# SFT_MotorController1_2v.net
KiCad netlist of a schematic drawn in EAGLE
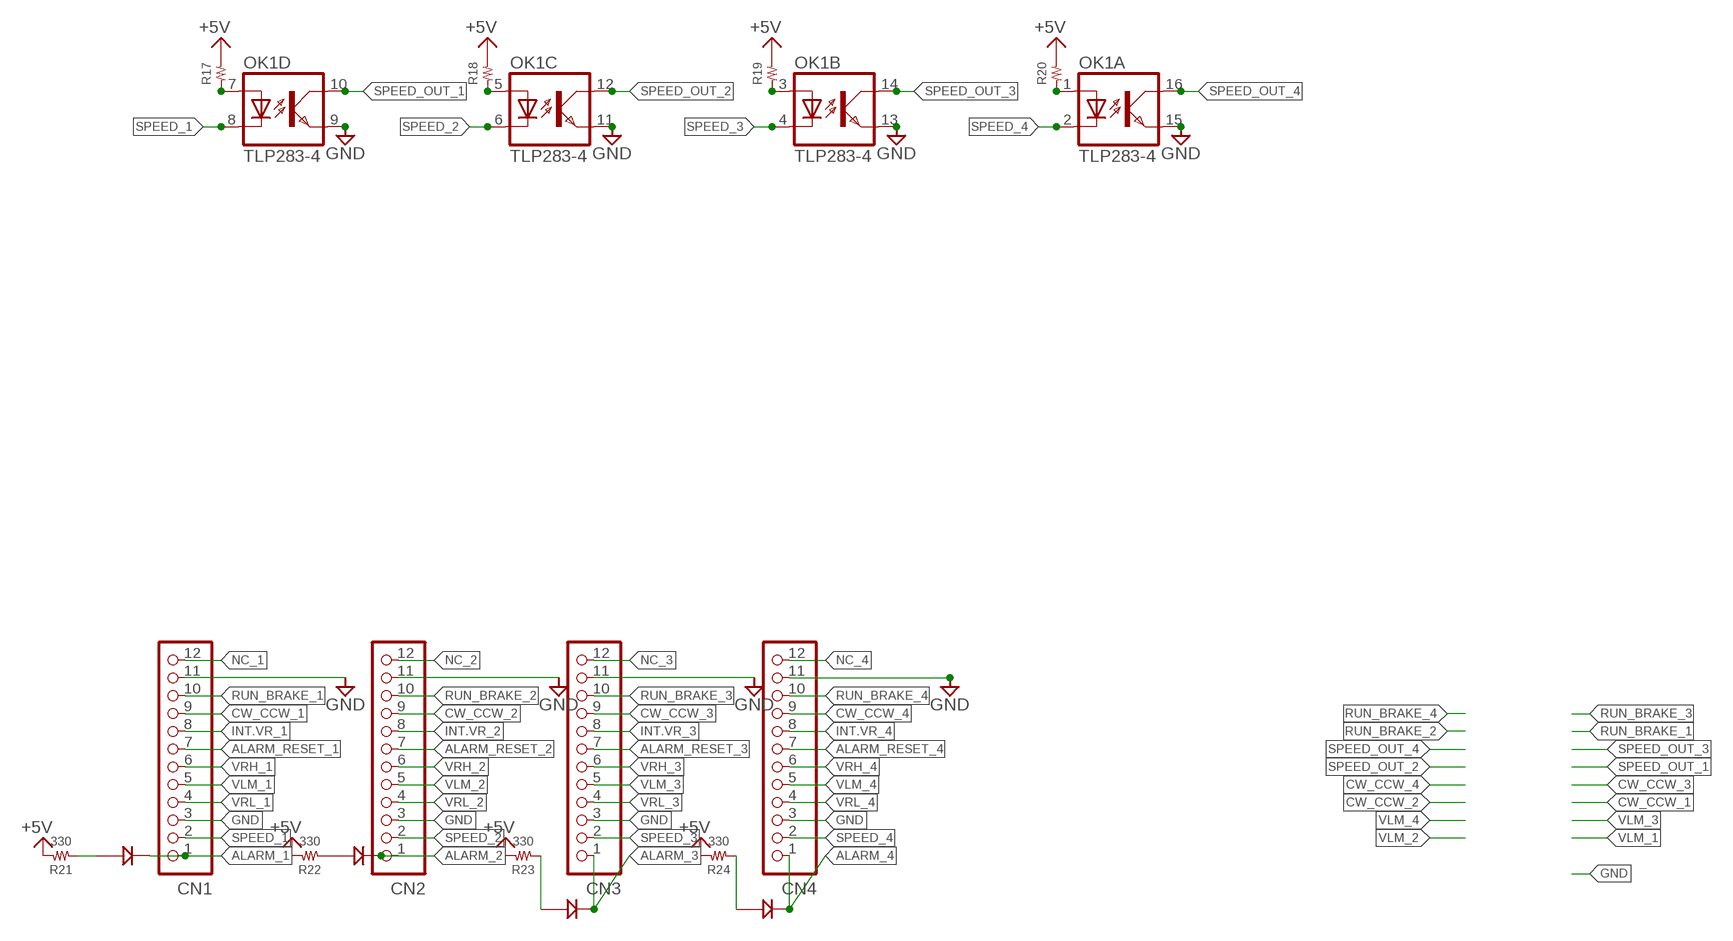
[diagram p0: schematic, sheet 1, part 1 of 2]
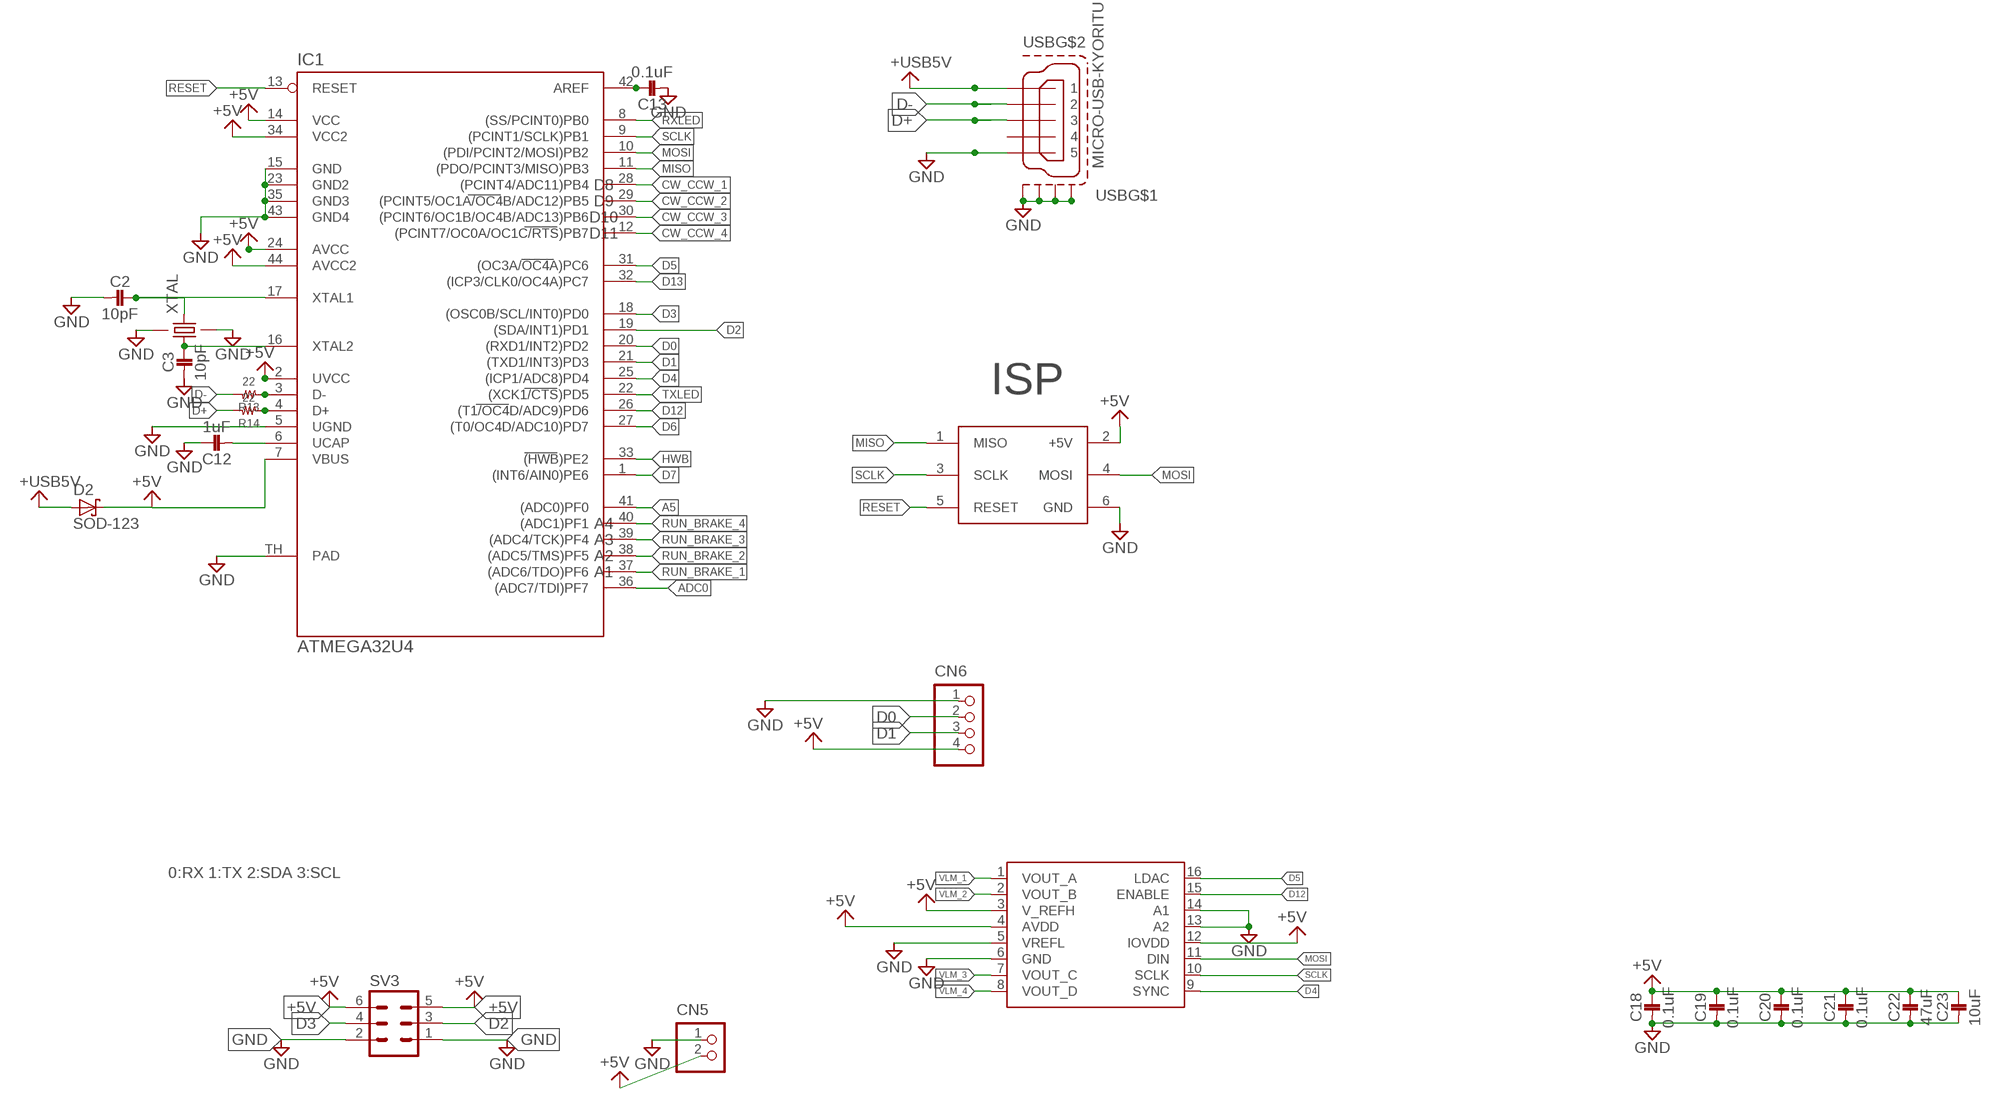
[diagram p1: schematic, sheet 1, part 2 of 2]

(export (version "E")
  (design (tool "Eeschema 10.0.6"))
  (components
    (comp (ref "C2")
      (value "10pF")
      (footprint "eagle-import:1005")
      (libsource (lib "eagle-import") (part "1005"))
    )
    (comp (ref "C3")
      (value "10pF")
      (footprint "eagle-import:1005")
      (libsource (lib "eagle-import") (part "1005"))
    )
    (comp (ref "C12")
      (value "1uF")
      (footprint "eagle-import:1005")
      (libsource (lib "eagle-import") (part "1005"))
    )
    (comp (ref "C13")
      (value "0.1uF")
      (footprint "eagle-import:1005")
      (libsource (lib "eagle-import") (part "1005"))
    )
    (comp (ref "C18")
      (value "0.1uF")
      (footprint "eagle-import:1005")
      (libsource (lib "eagle-import") (part "1005"))
    )
    (comp (ref "C19")
      (value "0.1uF")
      (footprint "eagle-import:1005")
      (libsource (lib "eagle-import") (part "1005"))
    )
    (comp (ref "C20")
      (value "0.1uF")
      (footprint "eagle-import:1005")
      (libsource (lib "eagle-import") (part "1005"))
    )
    (comp (ref "C21")
      (value "0.1uF")
      (footprint "eagle-import:1005")
      (libsource (lib "eagle-import") (part "1005"))
    )
    (comp (ref "C22")
      (value "47uF")
      (footprint "eagle-import:1608")
      (libsource (lib "eagle-import") (part "1608"))
    )
    (comp (ref "C23")
      (value "10uF")
      (footprint "eagle-import:1608")
      (libsource (lib "eagle-import") (part "1608"))
    )
    (comp (ref "CN1")
      (value "B12B-XASK-1")
      (footprint "eagle-import:B12B-XASK-1")
      (libsource (lib "eagle-import") (part "B12B-XASK-1"))
    )
    (comp (ref "CN2")
      (value "B12B-XASK-1")
      (footprint "eagle-import:B12B-XASK-1")
      (libsource (lib "eagle-import") (part "B12B-XASK-1"))
    )
    (comp (ref "CN3")
      (value "B12B-XASK-1")
      (footprint "eagle-import:B12B-XASK-1")
      (libsource (lib "eagle-import") (part "B12B-XASK-1"))
    )
    (comp (ref "CN4")
      (value "B12B-XASK-1")
      (footprint "eagle-import:B12B-XASK-1")
      (libsource (lib "eagle-import") (part "B12B-XASK-1"))
    )
    (comp (ref "CN5")
      (value "B2B-XASK-1")
      (footprint "eagle-import:B2B-XASK-1")
      (libsource (lib "eagle-import") (part "B2B-XASK-1"))
    )
    (comp (ref "CN6")
      (value "B4B-XASK-1")
      (footprint "eagle-import:B4B-XASK-1")
      (libsource (lib "eagle-import") (part "B4B-XASK-1"))
    )
    (comp (ref "D2")
      (value "SOD-123")
      (footprint "eagle-import:SOD_123")
      (libsource (lib "eagle-import") (part "SOD-123"))
    )
    (comp (ref "IC1")
      (value "ATMEGA32U4")
      (footprint "eagle-import:QFN-44-7X7")
      (libsource (lib "eagle-import") (part "ATMEGA32U4"))
    )
    (comp (ref "IC3")
      (value "DAC7564")
      (footprint "eagle-import:TSSOP16")
      (libsource (lib "eagle-import") (part "DAC7564"))
    )
    (comp (ref "OK1")
      (value "TLP283-4")
      (footprint "eagle-import:MINI-FLAT-16")
      (libsource (lib "eagle-import") (part "TLP283-4"))
    )
    (comp (ref "R13")
      (value "22")
      (footprint "eagle-import:1005")
      (libsource (lib "eagle-import") (part "RESISTOR_1005"))
    )
    (comp (ref "R14")
      (value "22")
      (footprint "eagle-import:1005")
      (libsource (lib "eagle-import") (part "RESISTOR_1005"))
    )
    (comp (ref "R17")
      (value "RESISTOR__SMD")
      (footprint "eagle-import:1608")
      (libsource (lib "eagle-import") (part "RESISTOR__SMD"))
    )
    (comp (ref "R18")
      (value "RESISTOR__SMD")
      (footprint "eagle-import:1608")
      (libsource (lib "eagle-import") (part "RESISTOR__SMD"))
    )
    (comp (ref "R19")
      (value "RESISTOR__SMD")
      (footprint "eagle-import:1608")
      (libsource (lib "eagle-import") (part "RESISTOR__SMD"))
    )
    (comp (ref "R20")
      (value "RESISTOR__SMD")
      (footprint "eagle-import:1608")
      (libsource (lib "eagle-import") (part "RESISTOR__SMD"))
    )
    (comp (ref "R21")
      (value "330")
      (footprint "eagle-import:1608")
      (libsource (lib "eagle-import") (part "RESISTOR__SMD"))
    )
    (comp (ref "R22")
      (value "330")
      (footprint "eagle-import:1608")
      (libsource (lib "eagle-import") (part "RESISTOR__SMD"))
    )
    (comp (ref "R23")
      (value "330")
      (footprint "eagle-import:1608")
      (libsource (lib "eagle-import") (part "RESISTOR__SMD"))
    )
    (comp (ref "R24")
      (value "330")
      (footprint "eagle-import:1608")
      (libsource (lib "eagle-import") (part "RESISTOR__SMD"))
    )
    (comp (ref "SV3")
      (value "ML6")
      (footprint "eagle-import:ML6")
      (libsource (lib "eagle-import") (part "ML6"))
    )
    (comp (ref "U$8")
      (value "ICSP")
      (footprint "eagle-import:ICSP")
      (libsource (lib "eagle-import") (part "ICSP"))
    )
    (comp (ref "U$36")
      (value "3MMLED")
      (footprint "eagle-import:3MM")
      (libsource (lib "eagle-import") (part "3MMLED"))
    )
    (comp (ref "U$37")
      (value "3MMLED")
      (footprint "eagle-import:3MM")
      (libsource (lib "eagle-import") (part "3MMLED"))
    )
    (comp (ref "U$38")
      (value "3MMLED")
      (footprint "eagle-import:3MM")
      (libsource (lib "eagle-import") (part "3MMLED"))
    )
    (comp (ref "U$39")
      (value "3MMLED")
      (footprint "eagle-import:3MM")
      (libsource (lib "eagle-import") (part "3MMLED"))
    )
    (comp (ref "USB")
      (value "MICRO-USB-KYORITU")
      (footprint "eagle-import:ZX62R-B-5P")
      (libsource (lib "eagle-import") (part "MICRO-USB-KYORITU"))
    )
    (comp (ref "XTAL")
      (value "FA-238")
      (footprint "eagle-import:FA-238")
      (libsource (lib "eagle-import") (part "FA-238"))
    )
  )
  (nets
    (net (code "1") (name "+5V") (class "Default")
      (node (ref "C18") (pin "1") (pinfunction "1_1") (pintype "passive"))
      (node (ref "C19") (pin "1") (pinfunction "1_1") (pintype "passive"))
      (node (ref "C20") (pin "1") (pinfunction "1_1") (pintype "passive"))
      (node (ref "C21") (pin "1") (pinfunction "1_1") (pintype "passive"))
      (node (ref "C22") (pin "P$1") (pinfunction "1_P$1") (pintype "passive"))
      (node (ref "C23") (pin "P$1") (pinfunction "1_P$1") (pintype "passive"))
      (node (ref "CN5") (pin "2") (pinfunction "2_2") (pintype "passive"))
      (node (ref "CN6") (pin "4") (pinfunction "4_4") (pintype "passive"))
      (node (ref "D2") (pin "C") (pinfunction "C_C") (pintype "passive"))
      (node (ref "IC1") (pin "14") (pinfunction "VCC_14") (pintype "bidirectional"))
      (node (ref "IC1") (pin "2") (pinfunction "UVCC_2") (pintype "bidirectional"))
      (node (ref "IC1") (pin "24") (pinfunction "AVCC_24") (pintype "bidirectional"))
      (node (ref "IC1") (pin "34") (pinfunction "VCC2_34") (pintype "bidirectional"))
      (node (ref "IC1") (pin "44") (pinfunction "AVCC2_44") (pintype "bidirectional"))
      (node (ref "IC1") (pin "7") (pinfunction "VBUS_7") (pintype "bidirectional"))
      (node (ref "IC3") (pin "12") (pinfunction "IOVDD_12") (pintype "bidirectional"))
      (node (ref "IC3") (pin "3") (pinfunction "V_REFH_3") (pintype "bidirectional"))
      (node (ref "IC3") (pin "4") (pinfunction "AVDD_4") (pintype "bidirectional"))
      (node (ref "R17") (pin "2") (pinfunction "P$2_2") (pintype "passive"))
      (node (ref "R18") (pin "2") (pinfunction "P$2_2") (pintype "passive"))
      (node (ref "R19") (pin "2") (pinfunction "P$2_2") (pintype "passive"))
      (node (ref "R20") (pin "2") (pinfunction "P$2_2") (pintype "passive"))
      (node (ref "R21") (pin "2") (pinfunction "P$2_2") (pintype "passive"))
      (node (ref "R22") (pin "2") (pinfunction "P$2_2") (pintype "passive"))
      (node (ref "R23") (pin "2") (pinfunction "P$2_2") (pintype "passive"))
      (node (ref "R24") (pin "2") (pinfunction "P$2_2") (pintype "passive"))
      (node (ref "SV3") (pin "5") (pinfunction "5_5") (pintype "passive"))
      (node (ref "SV3") (pin "6") (pinfunction "6_6") (pintype "passive"))
      (node (ref "U$8") (pin "2") (pinfunction "+5V_2") (pintype "bidirectional"))
    )
    (net (code "2") (name "+USB5V") (class "Default")
      (node (ref "D2") (pin "A") (pinfunction "A_A") (pintype "passive"))
      (node (ref "USB") (pin "5") (pinfunction "1_5") (pintype "input"))
    )
    (net (code "3") (name "A5") (class "Default")
      (node (ref "IC1") (pin "41") (pinfunction "(ADC0)PF0_41") (pintype "bidirectional"))
    )
    (net (code "4") (name "ADC0") (class "Default")
      (node (ref "IC1") (pin "36") (pinfunction "(ADC7/TDI)PF7_36") (pintype "bidirectional"))
    )
    (net (code "5") (name "ALARM_1") (class "Default")
      (node (ref "CN1") (pin "1") (pinfunction "1_1") (pintype "passive"))
      (node (ref "U$37") (pin "K") (pinfunction "K_K") (pintype "bidirectional"))
    )
    (net (code "6") (name "ALARM_2") (class "Default")
      (node (ref "CN2") (pin "1") (pinfunction "1_1") (pintype "passive"))
      (node (ref "U$38") (pin "K") (pinfunction "K_K") (pintype "bidirectional"))
    )
    (net (code "7") (name "ALARM_3") (class "Default")
      (node (ref "CN3") (pin "1") (pinfunction "1_1") (pintype "passive"))
      (node (ref "U$36") (pin "K") (pinfunction "K_K") (pintype "bidirectional"))
    )
    (net (code "8") (name "ALARM_4") (class "Default")
      (node (ref "CN4") (pin "1") (pinfunction "1_1") (pintype "passive"))
      (node (ref "U$39") (pin "K") (pinfunction "K_K") (pintype "bidirectional"))
    )
    (net (code "9") (name "ALARM_RESET_1") (class "Default")
      (node (ref "CN1") (pin "7") (pinfunction "7_7") (pintype "passive"))
    )
    (net (code "10") (name "ALARM_RESET_2") (class "Default")
      (node (ref "CN2") (pin "7") (pinfunction "7_7") (pintype "passive"))
    )
    (net (code "11") (name "ALARM_RESET_3") (class "Default")
      (node (ref "CN3") (pin "7") (pinfunction "7_7") (pintype "passive"))
    )
    (net (code "12") (name "ALARM_RESET_4") (class "Default")
      (node (ref "CN4") (pin "7") (pinfunction "7_7") (pintype "passive"))
    )
    (net (code "13") (name "CW_CCW_1") (class "Default")
      (node (ref "CN1") (pin "9") (pinfunction "9_9") (pintype "passive"))
      (node (ref "IC1") (pin "28") (pinfunction "(PCINT4/ADC11)PB4_28") (pintype "bidirectional"))
    )
    (net (code "14") (name "CW_CCW_2") (class "Default")
      (node (ref "CN2") (pin "9") (pinfunction "9_9") (pintype "passive"))
      (node (ref "IC1") (pin "29") (pinfunction "(PCINT5/OC1A/OC4B/ADC12)PB5_29") (pintype "bidirectional"))
    )
    (net (code "15") (name "CW_CCW_3") (class "Default")
      (node (ref "CN3") (pin "9") (pinfunction "9_9") (pintype "passive"))
      (node (ref "IC1") (pin "30") (pinfunction "(PCINT6/OC1B/OC4B/ADC13)PB6_30") (pintype "bidirectional"))
    )
    (net (code "16") (name "CW_CCW_4") (class "Default")
      (node (ref "CN4") (pin "9") (pinfunction "9_9") (pintype "passive"))
      (node (ref "IC1") (pin "12") (pinfunction "(PCINT7/OC0A/OC1C/RTS)PB7_12") (pintype "bidirectional"))
    )
    (net (code "17") (name "D+") (class "Default")
      (node (ref "R14") (pin "2") (pinfunction "P$2_2") (pintype "passive"))
      (node (ref "USB") (pin "3") (pinfunction "3_3") (pintype "input"))
    )
    (net (code "18") (name "D-") (class "Default")
      (node (ref "R13") (pin "2") (pinfunction "P$2_2") (pintype "passive"))
      (node (ref "USB") (pin "4") (pinfunction "2_4") (pintype "input"))
    )
    (net (code "19") (name "D0") (class "Default")
      (node (ref "CN6") (pin "2") (pinfunction "2_2") (pintype "passive"))
      (node (ref "IC1") (pin "20") (pinfunction "(RXD1/INT2)PD2_20") (pintype "bidirectional"))
    )
    (net (code "20") (name "D1") (class "Default")
      (node (ref "CN6") (pin "3") (pinfunction "3_3") (pintype "passive"))
      (node (ref "IC1") (pin "21") (pinfunction "(TXD1/INT3)PD3_21") (pintype "bidirectional"))
    )
    (net (code "21") (name "D2") (class "Default")
      (node (ref "IC1") (pin "19") (pinfunction "(SDA/INT1)PD1_19") (pintype "bidirectional"))
      (node (ref "SV3") (pin "3") (pinfunction "3_3") (pintype "passive"))
    )
    (net (code "22") (name "D3") (class "Default")
      (node (ref "IC1") (pin "18") (pinfunction "(OSC0B/SCL/INT0)PD0_18") (pintype "bidirectional"))
      (node (ref "SV3") (pin "4") (pinfunction "4_4") (pintype "passive"))
    )
    (net (code "23") (name "D4") (class "Default")
      (node (ref "IC1") (pin "25") (pinfunction "(ICP1/ADC8)PD4_25") (pintype "bidirectional"))
      (node (ref "IC3") (pin "9") (pinfunction "SYNC_9") (pintype "bidirectional"))
    )
    (net (code "24") (name "D5") (class "Default")
      (node (ref "IC1") (pin "31") (pinfunction "(OC3A/OC4A)PC6_31") (pintype "bidirectional"))
      (node (ref "IC3") (pin "16") (pinfunction "LDAC_16") (pintype "bidirectional"))
    )
    (net (code "25") (name "D6") (class "Default")
      (node (ref "IC1") (pin "27") (pinfunction "(T0/OC4D/ADC10)PD7_27") (pintype "bidirectional"))
    )
    (net (code "26") (name "D7") (class "Default")
      (node (ref "IC1") (pin "1") (pinfunction "(INT6/AIN0)PE6_1") (pintype "bidirectional"))
    )
    (net (code "27") (name "D12") (class "Default")
      (node (ref "IC1") (pin "26") (pinfunction "(T1/OC4D/ADC9)PD6_26") (pintype "bidirectional"))
      (node (ref "IC3") (pin "15") (pinfunction "ENABLE_15") (pintype "bidirectional"))
    )
    (net (code "28") (name "D13") (class "Default")
      (node (ref "IC1") (pin "32") (pinfunction "(ICP3/CLK0/OC4A)PC7_32") (pintype "bidirectional"))
    )
    (net (code "29") (name "GND") (class "Default")
      (node (ref "C12") (pin "1") (pinfunction "1_1") (pintype "passive"))
      (node (ref "C13") (pin "2") (pinfunction "2_2") (pintype "passive"))
      (node (ref "C18") (pin "2") (pinfunction "2_2") (pintype "passive"))
      (node (ref "C19") (pin "2") (pinfunction "2_2") (pintype "passive"))
      (node (ref "C2") (pin "2") (pinfunction "2_2") (pintype "passive"))
      (node (ref "C20") (pin "2") (pinfunction "2_2") (pintype "passive"))
      (node (ref "C21") (pin "2") (pinfunction "2_2") (pintype "passive"))
      (node (ref "C22") (pin "P$2") (pinfunction "2_P$2") (pintype "passive"))
      (node (ref "C23") (pin "P$2") (pinfunction "2_P$2") (pintype "passive"))
      (node (ref "C3") (pin "2") (pinfunction "2_2") (pintype "passive"))
      (node (ref "CN1") (pin "11") (pinfunction "11_11") (pintype "passive"))
      (node (ref "CN1") (pin "3") (pinfunction "3_3") (pintype "passive"))
      (node (ref "CN2") (pin "11") (pinfunction "11_11") (pintype "passive"))
      (node (ref "CN2") (pin "3") (pinfunction "3_3") (pintype "passive"))
      (node (ref "CN3") (pin "11") (pinfunction "11_11") (pintype "passive"))
      (node (ref "CN3") (pin "3") (pinfunction "3_3") (pintype "passive"))
      (node (ref "CN4") (pin "11") (pinfunction "11_11") (pintype "passive"))
      (node (ref "CN4") (pin "3") (pinfunction "3_3") (pintype "passive"))
      (node (ref "CN5") (pin "1") (pinfunction "1_1") (pintype "passive"))
      (node (ref "CN6") (pin "1") (pinfunction "1_1") (pintype "passive"))
      (node (ref "IC1") (pin "15") (pinfunction "GND_15") (pintype "bidirectional"))
      (node (ref "IC1") (pin "23") (pinfunction "GND2_23") (pintype "bidirectional"))
      (node (ref "IC1") (pin "35") (pinfunction "GND3_35") (pintype "bidirectional"))
      (node (ref "IC1") (pin "43") (pinfunction "GND4_43") (pintype "bidirectional"))
      (node (ref "IC1") (pin "5") (pinfunction "UGND_5") (pintype "bidirectional"))
      (node (ref "IC1") (pin "TH") (pinfunction "PAD_TH") (pintype "bidirectional"))
      (node (ref "IC3") (pin "13") (pinfunction "A2_13") (pintype "bidirectional"))
      (node (ref "IC3") (pin "14") (pinfunction "A1_14") (pintype "bidirectional"))
      (node (ref "IC3") (pin "5") (pinfunction "VREFL_5") (pintype "bidirectional"))
      (node (ref "IC3") (pin "6") (pinfunction "GND_6") (pintype "bidirectional"))
      (node (ref "OK1") (pin "11") (pinfunction "EMIT_11") (pintype "passive"))
      (node (ref "OK1") (pin "13") (pinfunction "EMIT_13") (pintype "passive"))
      (node (ref "OK1") (pin "15") (pinfunction "EMIT_15") (pintype "passive"))
      (node (ref "OK1") (pin "9") (pinfunction "EMIT_9") (pintype "passive"))
      (node (ref "SV3") (pin "1") (pinfunction "1_1") (pintype "passive"))
      (node (ref "SV3") (pin "2") (pinfunction "2_2") (pintype "passive"))
      (node (ref "U$8") (pin "6") (pinfunction "GND_6") (pintype "bidirectional"))
      (node (ref "USB") (pin "1") (pinfunction "5_1") (pintype "input"))
      (node (ref "USB") (pin "M1") (pinfunction "S1_M1") (pintype "passive"))
      (node (ref "USB") (pin "M2") (pinfunction "S2_M2") (pintype "passive"))
      (node (ref "USB") (pin "M3") (pinfunction "S3_M3") (pintype "passive"))
      (node (ref "USB") (pin "M4") (pinfunction "S4_M4") (pintype "passive"))
      (node (ref "XTAL") (pin "2") (pinfunction "2_2") (pintype "bidirectional"))
      (node (ref "XTAL") (pin "4") (pinfunction "4_4") (pintype "bidirectional"))
    )
    (net (code "30") (name "HWB") (class "Default")
      (node (ref "IC1") (pin "33") (pinfunction "(HWB)PE2_33") (pintype "bidirectional"))
    )
    (net (code "31") (name "INT.VR_1") (class "Default")
      (node (ref "CN1") (pin "8") (pinfunction "8_8") (pintype "passive"))
    )
    (net (code "32") (name "INT.VR_2") (class "Default")
      (node (ref "CN2") (pin "8") (pinfunction "8_8") (pintype "passive"))
    )
    (net (code "33") (name "INT.VR_3") (class "Default")
      (node (ref "CN3") (pin "8") (pinfunction "8_8") (pintype "passive"))
    )
    (net (code "34") (name "INT.VR_4") (class "Default")
      (node (ref "CN4") (pin "8") (pinfunction "8_8") (pintype "passive"))
    )
    (net (code "35") (name "MISO") (class "Default")
      (node (ref "IC1") (pin "11") (pinfunction "(PDO/PCINT3/MISO)PB3_11") (pintype "bidirectional"))
      (node (ref "U$8") (pin "1") (pinfunction "MISO_1") (pintype "bidirectional"))
    )
    (net (code "36") (name "MOSI") (class "Default")
      (node (ref "IC1") (pin "10") (pinfunction "(PDI/PCINT2/MOSI)PB2_10") (pintype "bidirectional"))
      (node (ref "IC3") (pin "11") (pinfunction "DIN_11") (pintype "bidirectional"))
      (node (ref "U$8") (pin "4") (pinfunction "MOSI_4") (pintype "bidirectional"))
    )
    (net (code "37") (name "NC_1") (class "Default")
      (node (ref "CN1") (pin "12") (pinfunction "12_12") (pintype "passive"))
    )
    (net (code "38") (name "NC_2") (class "Default")
      (node (ref "CN2") (pin "12") (pinfunction "12_12") (pintype "passive"))
    )
    (net (code "39") (name "NC_3") (class "Default")
      (node (ref "CN3") (pin "12") (pinfunction "12_12") (pintype "passive"))
    )
    (net (code "40") (name "NC_4") (class "Default")
      (node (ref "CN4") (pin "12") (pinfunction "12_12") (pintype "passive"))
    )
    (net (code "41") (name "Net-(IC1-AREF)") (class "Default")
      (node (ref "C13") (pin "1") (pinfunction "1_1") (pintype "passive"))
      (node (ref "IC1") (pin "42") (pinfunction "AREF_42") (pintype "bidirectional"))
    )
    (net (code "42") (name "Net-(IC1-D+)") (class "Default")
      (node (ref "IC1") (pin "4") (pinfunction "D+_4") (pintype "bidirectional"))
      (node (ref "R14") (pin "1") (pinfunction "P$1_1") (pintype "passive"))
    )
    (net (code "43") (name "Net-(IC1-D-)") (class "Default")
      (node (ref "IC1") (pin "3") (pinfunction "D-_3") (pintype "bidirectional"))
      (node (ref "R13") (pin "1") (pinfunction "P$1_1") (pintype "passive"))
    )
    (net (code "44") (name "Net-(IC1-UCAP)") (class "Default")
      (node (ref "C12") (pin "2") (pinfunction "2_2") (pintype "passive"))
      (node (ref "IC1") (pin "6") (pinfunction "UCAP_6") (pintype "bidirectional"))
    )
    (net (code "45") (name "Net-(IC1-XTAL1)") (class "Default")
      (node (ref "C2") (pin "1") (pinfunction "1_1") (pintype "passive"))
      (node (ref "IC1") (pin "17") (pinfunction "XTAL1_17") (pintype "bidirectional"))
      (node (ref "XTAL") (pin "3") (pinfunction "3_3") (pintype "passive"))
    )
    (net (code "46") (name "Net-(IC1-XTAL2)") (class "Default")
      (node (ref "C3") (pin "1") (pinfunction "1_1") (pintype "passive"))
      (node (ref "IC1") (pin "16") (pinfunction "XTAL2_16") (pintype "bidirectional"))
      (node (ref "XTAL") (pin "1") (pinfunction "1_1") (pintype "passive"))
    )
    (net (code "47") (name "Net-(OK1A-A)") (class "Default")
      (node (ref "OK1") (pin "1") (pinfunction "A_1") (pintype "passive"))
      (node (ref "R20") (pin "1") (pinfunction "P$1_1") (pintype "passive"))
    )
    (net (code "48") (name "Net-(OK1B-A)") (class "Default")
      (node (ref "OK1") (pin "3") (pinfunction "A_3") (pintype "passive"))
      (node (ref "R19") (pin "1") (pinfunction "P$1_1") (pintype "passive"))
    )
    (net (code "49") (name "Net-(OK1C-A)") (class "Default")
      (node (ref "OK1") (pin "5") (pinfunction "A_5") (pintype "passive"))
      (node (ref "R18") (pin "1") (pinfunction "P$1_1") (pintype "passive"))
    )
    (net (code "50") (name "Net-(OK1D-A)") (class "Default")
      (node (ref "OK1") (pin "7") (pinfunction "A_7") (pintype "passive"))
      (node (ref "R17") (pin "1") (pinfunction "P$1_1") (pintype "passive"))
    )
    (net (code "51") (name "Net-(R21-P$1)") (class "Default")
      (node (ref "R21") (pin "1") (pinfunction "P$1_1") (pintype "passive"))
      (node (ref "U$37") (pin "A") (pinfunction "A_A") (pintype "bidirectional"))
    )
    (net (code "52") (name "Net-(R22-P$1)") (class "Default")
      (node (ref "R22") (pin "1") (pinfunction "P$1_1") (pintype "passive"))
      (node (ref "U$38") (pin "A") (pinfunction "A_A") (pintype "bidirectional"))
    )
    (net (code "53") (name "Net-(R23-P$1)") (class "Default")
      (node (ref "R23") (pin "1") (pinfunction "P$1_1") (pintype "passive"))
      (node (ref "U$36") (pin "A") (pinfunction "A_A") (pintype "bidirectional"))
    )
    (net (code "54") (name "Net-(R24-P$1)") (class "Default")
      (node (ref "R24") (pin "1") (pinfunction "P$1_1") (pintype "passive"))
      (node (ref "U$39") (pin "A") (pinfunction "A_A") (pintype "bidirectional"))
    )
    (net (code "55") (name "RESET") (class "Default")
      (node (ref "IC1") (pin "13") (pinfunction "RESET_13") (pintype "bidirectional"))
      (node (ref "U$8") (pin "5") (pinfunction "RESET_5") (pintype "bidirectional"))
    )
    (net (code "56") (name "RUN_BRAKE_1") (class "Default")
      (node (ref "CN1") (pin "10") (pinfunction "10_10") (pintype "passive"))
      (node (ref "IC1") (pin "37") (pinfunction "(ADC6/TDO)PF6_37") (pintype "bidirectional"))
    )
    (net (code "57") (name "RUN_BRAKE_2") (class "Default")
      (node (ref "CN2") (pin "10") (pinfunction "10_10") (pintype "passive"))
      (node (ref "IC1") (pin "38") (pinfunction "(ADC5/TMS)PF5_38") (pintype "bidirectional"))
    )
    (net (code "58") (name "RUN_BRAKE_3") (class "Default")
      (node (ref "CN3") (pin "10") (pinfunction "10_10") (pintype "passive"))
      (node (ref "IC1") (pin "39") (pinfunction "(ADC4/TCK)PF4_39") (pintype "bidirectional"))
    )
    (net (code "59") (name "RUN_BRAKE_4") (class "Default")
      (node (ref "CN4") (pin "10") (pinfunction "10_10") (pintype "passive"))
      (node (ref "IC1") (pin "40") (pinfunction "(ADC1)PF1_40") (pintype "bidirectional"))
    )
    (net (code "60") (name "RXLED") (class "Default")
      (node (ref "IC1") (pin "8") (pinfunction "(SS/PCINT0)PB0_8") (pintype "bidirectional"))
    )
    (net (code "61") (name "SCLK") (class "Default")
      (node (ref "IC1") (pin "9") (pinfunction "(PCINT1/SCLK)PB1_9") (pintype "bidirectional"))
      (node (ref "IC3") (pin "10") (pinfunction "SCLK_10") (pintype "bidirectional"))
      (node (ref "U$8") (pin "3") (pinfunction "SCLK_3") (pintype "bidirectional"))
    )
    (net (code "62") (name "SPEED_1") (class "Default")
      (node (ref "CN1") (pin "2") (pinfunction "2_2") (pintype "passive"))
      (node (ref "OK1") (pin "8") (pinfunction "C_8") (pintype "passive"))
    )
    (net (code "63") (name "SPEED_2") (class "Default")
      (node (ref "CN2") (pin "2") (pinfunction "2_2") (pintype "passive"))
      (node (ref "OK1") (pin "6") (pinfunction "C_6") (pintype "passive"))
    )
    (net (code "64") (name "SPEED_3") (class "Default")
      (node (ref "CN3") (pin "2") (pinfunction "2_2") (pintype "passive"))
      (node (ref "OK1") (pin "4") (pinfunction "C_4") (pintype "passive"))
    )
    (net (code "65") (name "SPEED_4") (class "Default")
      (node (ref "CN4") (pin "2") (pinfunction "2_2") (pintype "passive"))
      (node (ref "OK1") (pin "2") (pinfunction "C_2") (pintype "passive"))
    )
    (net (code "66") (name "SPEED_OUT_1") (class "Default")
      (node (ref "OK1") (pin "10") (pinfunction "COL_10") (pintype "passive"))
    )
    (net (code "67") (name "SPEED_OUT_2") (class "Default")
      (node (ref "OK1") (pin "12") (pinfunction "COL_12") (pintype "passive"))
    )
    (net (code "68") (name "SPEED_OUT_3") (class "Default")
      (node (ref "OK1") (pin "14") (pinfunction "COL_14") (pintype "passive"))
    )
    (net (code "69") (name "SPEED_OUT_4") (class "Default")
      (node (ref "OK1") (pin "16") (pinfunction "COL_16") (pintype "passive"))
    )
    (net (code "70") (name "TXLED") (class "Default")
      (node (ref "IC1") (pin "22") (pinfunction "(XCK1/CTS)PD5_22") (pintype "bidirectional"))
    )
    (net (code "71") (name "VLM_1") (class "Default")
      (node (ref "CN1") (pin "5") (pinfunction "5_5") (pintype "passive"))
      (node (ref "IC3") (pin "1") (pinfunction "VOUT_A_1") (pintype "bidirectional"))
    )
    (net (code "72") (name "VLM_2") (class "Default")
      (node (ref "CN2") (pin "5") (pinfunction "5_5") (pintype "passive"))
      (node (ref "IC3") (pin "2") (pinfunction "VOUT_B_2") (pintype "bidirectional"))
    )
    (net (code "73") (name "VLM_3") (class "Default")
      (node (ref "CN3") (pin "5") (pinfunction "5_5") (pintype "passive"))
      (node (ref "IC3") (pin "7") (pinfunction "VOUT_C_7") (pintype "bidirectional"))
    )
    (net (code "74") (name "VLM_4") (class "Default")
      (node (ref "CN4") (pin "5") (pinfunction "5_5") (pintype "passive"))
      (node (ref "IC3") (pin "8") (pinfunction "VOUT_D_8") (pintype "bidirectional"))
    )
    (net (code "75") (name "VRH_1") (class "Default")
      (node (ref "CN1") (pin "6") (pinfunction "6_6") (pintype "passive"))
    )
    (net (code "76") (name "VRH_2") (class "Default")
      (node (ref "CN2") (pin "6") (pinfunction "6_6") (pintype "passive"))
    )
    (net (code "77") (name "VRH_3") (class "Default")
      (node (ref "CN3") (pin "6") (pinfunction "6_6") (pintype "passive"))
    )
    (net (code "78") (name "VRH_4") (class "Default")
      (node (ref "CN4") (pin "6") (pinfunction "6_6") (pintype "passive"))
    )
    (net (code "79") (name "VRL_1") (class "Default")
      (node (ref "CN1") (pin "4") (pinfunction "4_4") (pintype "passive"))
    )
    (net (code "80") (name "VRL_2") (class "Default")
      (node (ref "CN2") (pin "4") (pinfunction "4_4") (pintype "passive"))
    )
    (net (code "81") (name "VRL_3") (class "Default")
      (node (ref "CN3") (pin "4") (pinfunction "4_4") (pintype "passive"))
    )
    (net (code "82") (name "VRL_4") (class "Default")
      (node (ref "CN4") (pin "4") (pinfunction "4_4") (pintype "passive"))
    )
    (net (code "83") (name "unconnected-(USBB-4-Pad2)") (class "Default")
      (node (ref "USB") (pin "2") (pinfunction "4_2") (pintype "input"))
    )
  )
)
